# PET_Hat_Schematic.net
KiCad netlist of a schematic drawn in EAGLE
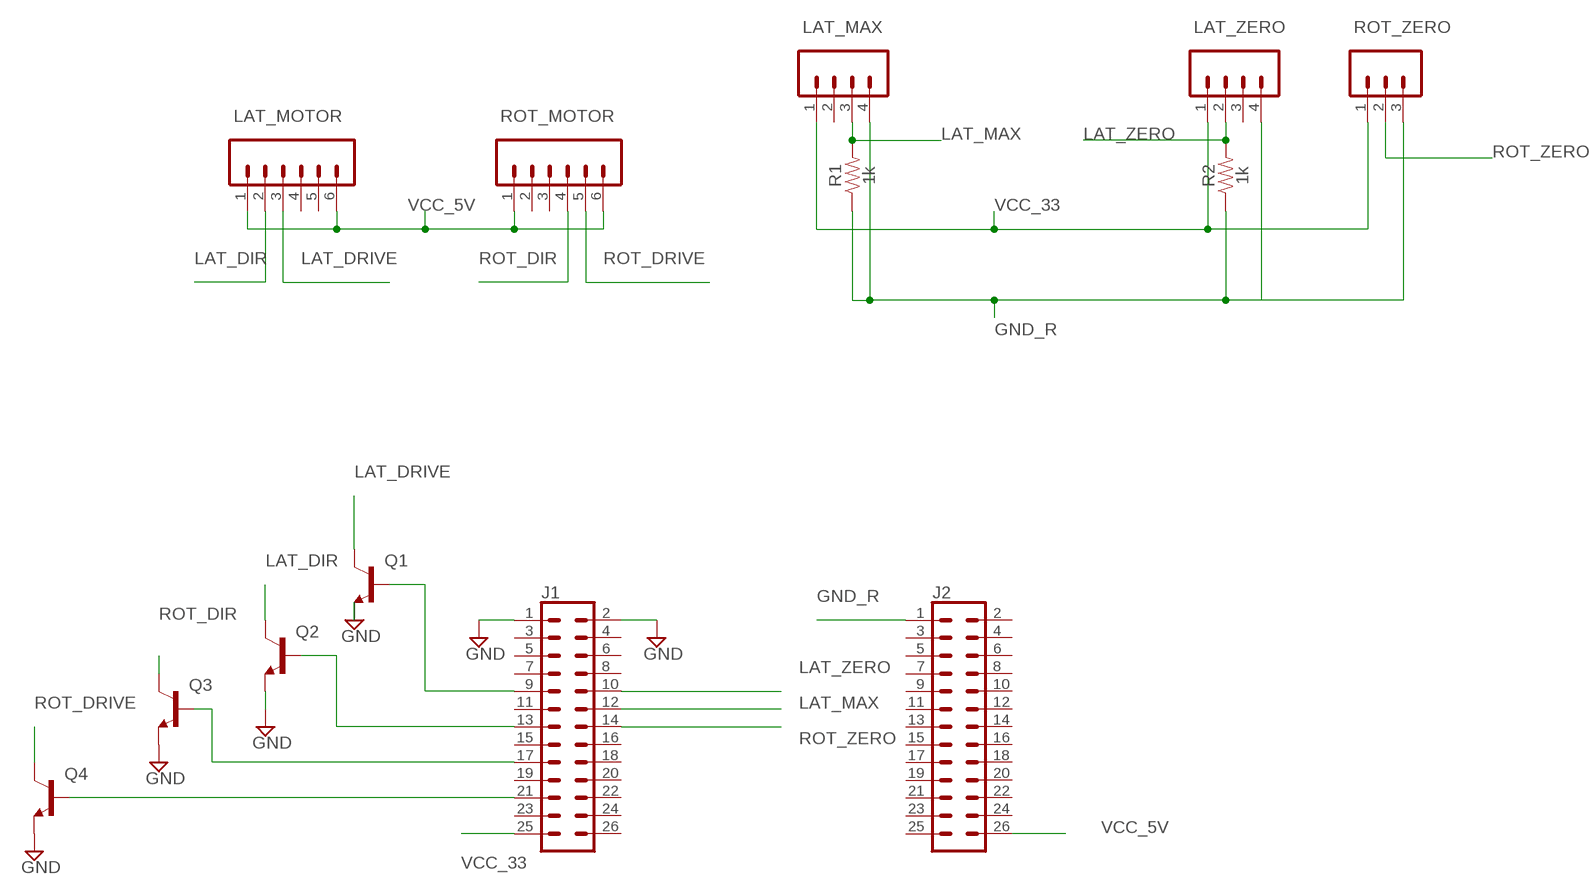
[diagram p0: schematic, sheet 1]

(export (version "E")
  (design (tool "Eeschema 10.0.6"))
  (components
    (comp (ref "J1")
      (value "CONN_13X22X13")
      (footprint "eagle-import:2X13")
      (libsource (lib "eagle-import") (part "CONN_13X22X13"))
    )
    (comp (ref "J2")
      (value "CONN_13X22X13")
      (footprint "eagle-import:2X13")
      (libsource (lib "eagle-import") (part "CONN_13X22X13"))
    )
    (comp (ref "LAT_MAX")
      (value "CONN_04POLAR")
      (footprint "eagle-import:MOLEX-1X4")
      (libsource (lib "eagle-import") (part "CONN_04POLAR"))
    )
    (comp (ref "LAT_MOTOR")
      (value "CONN_06POLAR")
      (footprint "eagle-import:MOLEX-1X6")
      (libsource (lib "eagle-import") (part "CONN_06POLAR"))
    )
    (comp (ref "LAT_ZERO")
      (value "CONN_04POLAR")
      (footprint "eagle-import:MOLEX-1X4")
      (libsource (lib "eagle-import") (part "CONN_04POLAR"))
    )
    (comp (ref "Q1")
      (value "2N3904")
      (footprint "eagle-import:TO92")
      (libsource (lib "eagle-import") (part "2N3904"))
    )
    (comp (ref "Q2")
      (value "2N3904")
      (footprint "eagle-import:TO92")
      (libsource (lib "eagle-import") (part "2N3904"))
    )
    (comp (ref "Q3")
      (value "2N3904")
      (footprint "eagle-import:TO92")
      (libsource (lib "eagle-import") (part "2N3904"))
    )
    (comp (ref "Q4")
      (value "2N3904")
      (footprint "eagle-import:TO92")
      (libsource (lib "eagle-import") (part "2N3904"))
    )
    (comp (ref "R1")
      (value "1k")
      (footprint "eagle-import:AXIAL-0.3")
      (libsource (lib "eagle-import") (part "1KOHM-HORIZ-1/4W-5%"))
    )
    (comp (ref "R2")
      (value "1k")
      (footprint "eagle-import:AXIAL-0.3")
      (libsource (lib "eagle-import") (part "1KOHM-HORIZ-1/4W-5%"))
    )
    (comp (ref "ROT_MOTOR")
      (value "CONN_06POLAR")
      (footprint "eagle-import:MOLEX-1X6")
      (libsource (lib "eagle-import") (part "CONN_06POLAR"))
    )
    (comp (ref "ROT_ZERO")
      (value "CONN_03POLAR")
      (footprint "eagle-import:MOLEX-1X3")
      (libsource (lib "eagle-import") (part "CONN_03POLAR"))
    )
  )
  (nets
    (net (code "1") (name "/GND_R") (class "Default")
      (node (ref "J2") (pin "1") (pinfunction "1_1") (pintype "passive"))
      (node (ref "LAT_MAX") (pin "4") (pinfunction "4_4") (pintype "passive"))
      (node (ref "R1") (pin "P$1") (pinfunction "1_P$1") (pintype "passive"))
      (node (ref "R2") (pin "P$1") (pinfunction "1_P$1") (pintype "passive"))
      (node (ref "ROT_ZERO") (pin "3") (pinfunction "3_3") (pintype "passive"))
    )
    (net (code "2") (name "/LAT_DIR") (class "Default")
      (node (ref "LAT_MOTOR") (pin "2") (pinfunction "2_2") (pintype "passive"))
      (node (ref "Q2") (pin "1") (pinfunction "C_1") (pintype "passive"))
    )
    (net (code "3") (name "/LAT_DRIVE") (class "Default")
      (node (ref "LAT_MOTOR") (pin "3") (pinfunction "3_3") (pintype "passive"))
      (node (ref "Q1") (pin "1") (pinfunction "C_1") (pintype "passive"))
    )
    (net (code "4") (name "/LAT_MAX") (class "Default")
      (node (ref "J1") (pin "12") (pinfunction "12_12") (pintype "passive"))
      (node (ref "LAT_MAX") (pin "3") (pinfunction "3_3") (pintype "passive"))
      (node (ref "R1") (pin "P$2") (pinfunction "2_P$2") (pintype "passive"))
    )
    (net (code "5") (name "/LAT_ZERO") (class "Default")
      (node (ref "J1") (pin "10") (pinfunction "10_10") (pintype "passive"))
      (node (ref "LAT_ZERO") (pin "2") (pinfunction "2_2") (pintype "passive"))
      (node (ref "R2") (pin "P$2") (pinfunction "2_P$2") (pintype "passive"))
    )
    (net (code "6") (name "/ROT_DIR") (class "Default")
      (node (ref "Q3") (pin "1") (pinfunction "C_1") (pintype "passive"))
      (node (ref "ROT_MOTOR") (pin "4") (pinfunction "4_4") (pintype "passive"))
    )
    (net (code "7") (name "/ROT_DRIVE") (class "Default")
      (node (ref "Q4") (pin "1") (pinfunction "C_1") (pintype "passive"))
      (node (ref "ROT_MOTOR") (pin "5") (pinfunction "5_5") (pintype "passive"))
    )
    (net (code "8") (name "/ROT_ZERO") (class "Default")
      (node (ref "J1") (pin "14") (pinfunction "14_14") (pintype "passive"))
      (node (ref "ROT_ZERO") (pin "2") (pinfunction "2_2") (pintype "passive"))
    )
    (net (code "9") (name "/VCC_5V") (class "Default")
      (node (ref "J2") (pin "26") (pinfunction "26_26") (pintype "passive"))
      (node (ref "LAT_MOTOR") (pin "1") (pinfunction "1_1") (pintype "passive"))
      (node (ref "LAT_MOTOR") (pin "6") (pinfunction "6_6") (pintype "passive"))
      (node (ref "ROT_MOTOR") (pin "1") (pinfunction "1_1") (pintype "passive"))
      (node (ref "ROT_MOTOR") (pin "6") (pinfunction "6_6") (pintype "passive"))
    )
    (net (code "10") (name "/VCC_33") (class "Default")
      (node (ref "J1") (pin "25") (pinfunction "25_25") (pintype "passive"))
      (node (ref "LAT_MAX") (pin "1") (pinfunction "1_1") (pintype "passive"))
      (node (ref "LAT_ZERO") (pin "1") (pinfunction "1_1") (pintype "passive"))
      (node (ref "ROT_ZERO") (pin "1") (pinfunction "1_1") (pintype "passive"))
    )
    (net (code "11") (name "GND") (class "Default")
      (node (ref "J1") (pin "1") (pinfunction "1_1") (pintype "passive"))
      (node (ref "J1") (pin "2") (pinfunction "2_2") (pintype "passive"))
      (node (ref "Q1") (pin "3") (pinfunction "E_3") (pintype "passive"))
      (node (ref "Q2") (pin "3") (pinfunction "E_3") (pintype "passive"))
      (node (ref "Q3") (pin "3") (pinfunction "E_3") (pintype "passive"))
      (node (ref "Q4") (pin "3") (pinfunction "E_3") (pintype "passive"))
    )
    (net (code "12") (name "Net-(Q1-B)") (class "Default")
      (node (ref "J1") (pin "9") (pinfunction "9_9") (pintype "passive"))
      (node (ref "Q1") (pin "2") (pinfunction "B_2") (pintype "passive"))
    )
    (net (code "13") (name "Net-(Q2-B)") (class "Default")
      (node (ref "J1") (pin "13") (pinfunction "13_13") (pintype "passive"))
      (node (ref "Q2") (pin "2") (pinfunction "B_2") (pintype "passive"))
    )
    (net (code "14") (name "Net-(Q3-B)") (class "Default")
      (node (ref "J1") (pin "17") (pinfunction "17_17") (pintype "passive"))
      (node (ref "Q3") (pin "2") (pinfunction "B_2") (pintype "passive"))
    )
    (net (code "15") (name "Net-(Q4-B)") (class "Default")
      (node (ref "J1") (pin "21") (pinfunction "21_21") (pintype "passive"))
      (node (ref "Q4") (pin "2") (pinfunction "B_2") (pintype "passive"))
    )
    (net (code "16") (name "unconnected-(J1-Pad3)") (class "Default")
      (node (ref "J1") (pin "3") (pinfunction "3_3") (pintype "passive"))
    )
    (net (code "17") (name "unconnected-(J1-Pad4)") (class "Default")
      (node (ref "J1") (pin "4") (pinfunction "4_4") (pintype "passive"))
    )
    (net (code "18") (name "unconnected-(J1-Pad5)") (class "Default")
      (node (ref "J1") (pin "5") (pinfunction "5_5") (pintype "passive"))
    )
    (net (code "19") (name "unconnected-(J1-Pad6)") (class "Default")
      (node (ref "J1") (pin "6") (pinfunction "6_6") (pintype "passive"))
    )
    (net (code "20") (name "unconnected-(J1-Pad7)") (class "Default")
      (node (ref "J1") (pin "7") (pinfunction "7_7") (pintype "passive"))
    )
    (net (code "21") (name "unconnected-(J1-Pad8)") (class "Default")
      (node (ref "J1") (pin "8") (pinfunction "8_8") (pintype "passive"))
    )
    (net (code "22") (name "unconnected-(J1-Pad11)") (class "Default")
      (node (ref "J1") (pin "11") (pinfunction "11_11") (pintype "passive"))
    )
    (net (code "23") (name "unconnected-(J1-Pad15)") (class "Default")
      (node (ref "J1") (pin "15") (pinfunction "15_15") (pintype "passive"))
    )
    (net (code "24") (name "unconnected-(J1-Pad16)") (class "Default")
      (node (ref "J1") (pin "16") (pinfunction "16_16") (pintype "passive"))
    )
    (net (code "25") (name "unconnected-(J1-Pad18)") (class "Default")
      (node (ref "J1") (pin "18") (pinfunction "18_18") (pintype "passive"))
    )
    (net (code "26") (name "unconnected-(J1-Pad19)") (class "Default")
      (node (ref "J1") (pin "19") (pinfunction "19_19") (pintype "passive"))
    )
    (net (code "27") (name "unconnected-(J1-Pad20)") (class "Default")
      (node (ref "J1") (pin "20") (pinfunction "20_20") (pintype "passive"))
    )
    (net (code "28") (name "unconnected-(J1-Pad22)") (class "Default")
      (node (ref "J1") (pin "22") (pinfunction "22_22") (pintype "passive"))
    )
    (net (code "29") (name "unconnected-(J1-Pad23)") (class "Default")
      (node (ref "J1") (pin "23") (pinfunction "23_23") (pintype "passive"))
    )
    (net (code "30") (name "unconnected-(J1-Pad24)") (class "Default")
      (node (ref "J1") (pin "24") (pinfunction "24_24") (pintype "passive"))
    )
    (net (code "31") (name "unconnected-(J1-Pad26)") (class "Default")
      (node (ref "J1") (pin "26") (pinfunction "26_26") (pintype "passive"))
    )
    (net (code "32") (name "unconnected-(J2-Pad2)") (class "Default")
      (node (ref "J2") (pin "2") (pinfunction "2_2") (pintype "passive"))
    )
    (net (code "33") (name "unconnected-(J2-Pad3)") (class "Default")
      (node (ref "J2") (pin "3") (pinfunction "3_3") (pintype "passive"))
    )
    (net (code "34") (name "unconnected-(J2-Pad4)") (class "Default")
      (node (ref "J2") (pin "4") (pinfunction "4_4") (pintype "passive"))
    )
    (net (code "35") (name "unconnected-(J2-Pad5)") (class "Default")
      (node (ref "J2") (pin "5") (pinfunction "5_5") (pintype "passive"))
    )
    (net (code "36") (name "unconnected-(J2-Pad6)") (class "Default")
      (node (ref "J2") (pin "6") (pinfunction "6_6") (pintype "passive"))
    )
    (net (code "37") (name "unconnected-(J2-Pad7)") (class "Default")
      (node (ref "J2") (pin "7") (pinfunction "7_7") (pintype "passive"))
    )
    (net (code "38") (name "unconnected-(J2-Pad8)") (class "Default")
      (node (ref "J2") (pin "8") (pinfunction "8_8") (pintype "passive"))
    )
    (net (code "39") (name "unconnected-(J2-Pad9)") (class "Default")
      (node (ref "J2") (pin "9") (pinfunction "9_9") (pintype "passive"))
    )
    (net (code "40") (name "unconnected-(J2-Pad10)") (class "Default")
      (node (ref "J2") (pin "10") (pinfunction "10_10") (pintype "passive"))
    )
    (net (code "41") (name "unconnected-(J2-Pad11)") (class "Default")
      (node (ref "J2") (pin "11") (pinfunction "11_11") (pintype "passive"))
    )
    (net (code "42") (name "unconnected-(J2-Pad12)") (class "Default")
      (node (ref "J2") (pin "12") (pinfunction "12_12") (pintype "passive"))
    )
    (net (code "43") (name "unconnected-(J2-Pad13)") (class "Default")
      (node (ref "J2") (pin "13") (pinfunction "13_13") (pintype "passive"))
    )
    (net (code "44") (name "unconnected-(J2-Pad14)") (class "Default")
      (node (ref "J2") (pin "14") (pinfunction "14_14") (pintype "passive"))
    )
    (net (code "45") (name "unconnected-(J2-Pad15)") (class "Default")
      (node (ref "J2") (pin "15") (pinfunction "15_15") (pintype "passive"))
    )
    (net (code "46") (name "unconnected-(J2-Pad16)") (class "Default")
      (node (ref "J2") (pin "16") (pinfunction "16_16") (pintype "passive"))
    )
    (net (code "47") (name "unconnected-(J2-Pad17)") (class "Default")
      (node (ref "J2") (pin "17") (pinfunction "17_17") (pintype "passive"))
    )
    (net (code "48") (name "unconnected-(J2-Pad18)") (class "Default")
      (node (ref "J2") (pin "18") (pinfunction "18_18") (pintype "passive"))
    )
    (net (code "49") (name "unconnected-(J2-Pad19)") (class "Default")
      (node (ref "J2") (pin "19") (pinfunction "19_19") (pintype "passive"))
    )
    (net (code "50") (name "unconnected-(J2-Pad20)") (class "Default")
      (node (ref "J2") (pin "20") (pinfunction "20_20") (pintype "passive"))
    )
    (net (code "51") (name "unconnected-(J2-Pad21)") (class "Default")
      (node (ref "J2") (pin "21") (pinfunction "21_21") (pintype "passive"))
    )
    (net (code "52") (name "unconnected-(J2-Pad22)") (class "Default")
      (node (ref "J2") (pin "22") (pinfunction "22_22") (pintype "passive"))
    )
    (net (code "53") (name "unconnected-(J2-Pad23)") (class "Default")
      (node (ref "J2") (pin "23") (pinfunction "23_23") (pintype "passive"))
    )
    (net (code "54") (name "unconnected-(J2-Pad24)") (class "Default")
      (node (ref "J2") (pin "24") (pinfunction "24_24") (pintype "passive"))
    )
    (net (code "55") (name "unconnected-(J2-Pad25)") (class "Default")
      (node (ref "J2") (pin "25") (pinfunction "25_25") (pintype "passive"))
    )
    (net (code "56") (name "unconnected-(LAT_MAX-Pad2)") (class "Default")
      (node (ref "LAT_MAX") (pin "2") (pinfunction "2_2") (pintype "passive"))
    )
    (net (code "57") (name "unconnected-(LAT_MOTOR-Pad4)") (class "Default")
      (node (ref "LAT_MOTOR") (pin "4") (pinfunction "4_4") (pintype "passive"))
    )
    (net (code "58") (name "unconnected-(LAT_MOTOR-Pad5)") (class "Default")
      (node (ref "LAT_MOTOR") (pin "5") (pinfunction "5_5") (pintype "passive"))
    )
    (net (code "59") (name "unconnected-(LAT_ZERO-Pad3)") (class "Default")
      (node (ref "LAT_ZERO") (pin "3") (pinfunction "3_3") (pintype "passive"))
    )
    (net (code "60") (name "unconnected-(LAT_ZERO-Pad4)") (class "Default")
      (node (ref "LAT_ZERO") (pin "4") (pinfunction "4_4") (pintype "passive"))
    )
    (net (code "61") (name "unconnected-(ROT_MOTOR-Pad2)") (class "Default")
      (node (ref "ROT_MOTOR") (pin "2") (pinfunction "2_2") (pintype "passive"))
    )
    (net (code "62") (name "unconnected-(ROT_MOTOR-Pad3)") (class "Default")
      (node (ref "ROT_MOTOR") (pin "3") (pinfunction "3_3") (pintype "passive"))
    )
  )
)
